# powersupply.net
KiCad netlist of a schematic drawn in Altium Designer
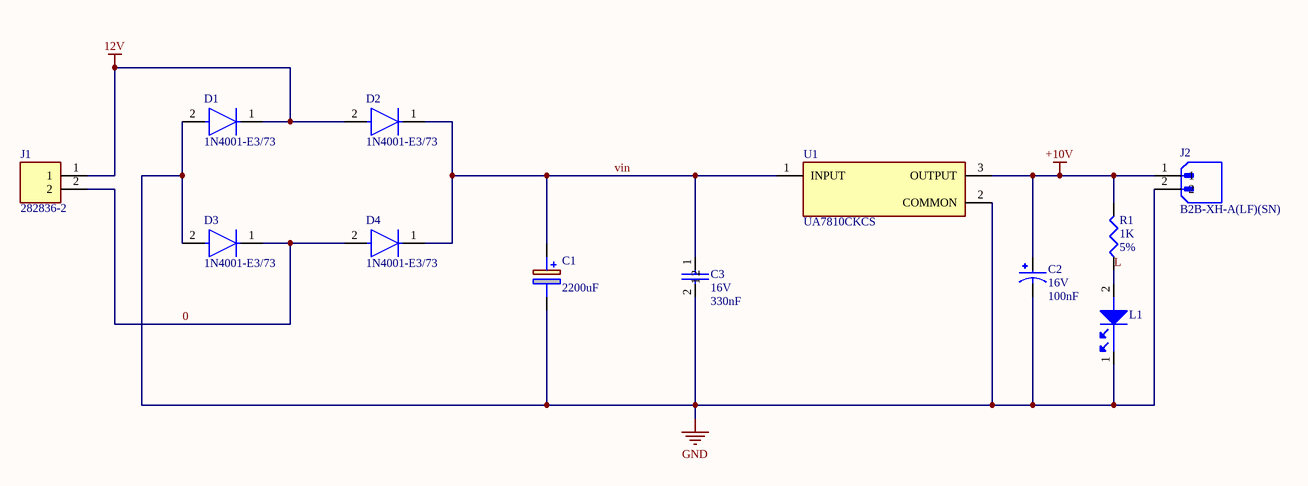
[diagram p0: powersupply.SchDoc]

(export (version "E")
  (design (tool "Eeschema 10.0.6"))
  (components
    (comp (ref "C1")
      (value "2200uF")
      (footprint "CAPPRD500W60D1275H2200")
      (description "Aluminum Electrolytic Capacitors Radial Miniature, Low Impedance, Automotive Grade")
      (fields
        (field (name "MOUSER PART NUMBER") "594-MAL217255222E3")
        (field (name "MANUFACTURER_PART_NUMBER") "MAL217255222E3")
      )
      (libsource (lib "powersupply") (part "MAL217255222E3"))
    )
    (comp (ref "C2")
      (value "100nF")
      (footprint "100nF_Capacitor - duplicate")
      (fields
        (field (name "MANUFACTURER") "Panasonic")
        (field (name "MANUFACTURER PART NUMBER") "EEA-GA1C100")
        (field (name "VOLTAGE") "16V")
        (field (name "CAPACITANCE") "100nF")
      )
      (libsource (lib "powersupply") (part "100nF"))
    )
    (comp (ref "C3")
      (value "330nF")
      (footprint "330nF_Capacitor - duplicate1")
      (description "Ceramic Capacitor, Ceramic, 16V, 10% +Tol, 10% -Tol, SL0, 120ppm/Cel TC, 330nF, Through Hole Mount")
      (fields
        (field (name "MANUFACTURER") "Vishay BCcomponents")
        (field (name "MANUFACTURER PART NUMBER") "S220K25SL0N63L6R")
        (field (name "VOLTAGE") "16V")
        (field (name "CAPACITANCE") "330nF")
      )
      (libsource (lib "powersupply") (part "330nF"))
    )
    (comp (ref "D1")
      (value "1N4001-E3/73")
      (footprint "FP-1N4001-E3-73-MFG")
      (description "DIODE GEN PURP 50V 1A DO204AL")
      (fields
        (field (name "MANUFACTURER") "Vishay")
        (field (name "OCTOPART") "https://octopart.com/1n4001-e3%2F73-vishay-42330130")
      )
      (libsource (lib "powersupply") (part "CMP-02540-000001-1"))
    )
    (comp (ref "D2")
      (value "1N4001-E3/73")
      (footprint "FP-1N4001-E3-73-MFG")
      (description "DIODE GEN PURP 50V 1A DO204AL")
      (fields
        (field (name "MANUFACTURER") "Vishay")
        (field (name "OCTOPART") "https://octopart.com/1n4001-e3%2F73-vishay-42330130")
      )
      (libsource (lib "powersupply") (part "CMP-02540-000001-1"))
    )
    (comp (ref "D3")
      (value "1N4001-E3/73")
      (footprint "FP-1N4001-E3-73-MFG")
      (description "DIODE GEN PURP 50V 1A DO204AL")
      (fields
        (field (name "MANUFACTURER") "Vishay")
        (field (name "OCTOPART") "https://octopart.com/1n4001-e3%2F73-vishay-42330130")
      )
      (libsource (lib "powersupply") (part "CMP-02540-000001-1"))
    )
    (comp (ref "D4")
      (value "1N4001-E3/73")
      (footprint "FP-1N4001-E3-73-MFG")
      (description "DIODE GEN PURP 50V 1A DO204AL")
      (fields
        (field (name "MANUFACTURER") "Vishay")
        (field (name "OCTOPART") "https://octopart.com/1n4001-e3%2F73-vishay-42330130")
      )
      (libsource (lib "powersupply") (part "CMP-02540-000001-1"))
    )
    (comp (ref "J1")
      (value "282836-2")
      (footprint "TE_282836-2")
      (fields (field (name "MF") "TE Connectivity"))
      (libsource (lib "powersupply") (part "282836-2"))
    )
    (comp (ref "J2")
      (value "B2B-XH-A(LF)(SN)")
      (footprint "JST_B2B-XH-A(LF)(SN)")
      (description "Connector Header Through Hole 2 position 0.098 (2.50mm)")
      (fields (field (name "MF") "JST Sales America Inc."))
      (libsource (lib "powersupply") (part "B2B-XH-A(LF)(SN)"))
    )
    (comp (ref "L1")
      (value "WP7113SRD/J4")
      (footprint "LEDRD254W57D500H1070")
      (description "LED Uni-Color SB. Red 660nm 2-Pin T-1 3/4 Bulk")
      (fields (field (name "MANUFACTURER") "Kingbright"))
      (libsource (lib "powersupply") (part "WP7113SRD/J4"))
    )
    (comp (ref "R1")
      (value "CFM12JT1K00")
      (footprint "Resister")
      (description "Fixed Resistor, Carbon Film, 0.5W, 1000ohm, 350V, 5% +/-Tol, -400,0ppm/Cel, Through Hole Mount")
      (fields
        (field (name "MANUFACTURER") "Stackpole Electronics")
        (field (name "POWER") "500mW")
        (field (name "RESISTANCE") "1K")
        (field (name "TOLERANCE") "5%")
      )
      (libsource (lib "powersupply") (part "CFM12JT1K00"))
    )
    (comp (ref "U1")
      (value "UA7810CKCS")
      (footprint "FP-KCS0003B-MFG")
      (description "IC REG LINEAR 10V 1.5A TO220-3")
      (libsource (lib "powersupply") (part "CMP-04917-000126-1"))
    )
  )
  (nets
    (net (code "1") (name "+10V") (class "Default")
      (node (ref "C2") (pin "1") (pinfunction "1_1") (pintype "passive"))
      (node (ref "J2") (pin "1") (pinfunction "1_1") (pintype "passive"))
      (node (ref "R1") (pin "2") (pinfunction "2_2") (pintype "passive"))
      (node (ref "U1") (pin "3") (pinfunction "OUTPUT_3") (pintype "power_in"))
    )
    (net (code "2") (name "/0") (class "Default")
      (node (ref "D3") (pin "1") (pinfunction "C_1") (pintype "passive"))
      (node (ref "D4") (pin "2") (pinfunction "A_2") (pintype "passive"))
      (node (ref "J1") (pin "2") (pinfunction "2_2") (pintype "passive"))
    )
    (net (code "3") (name "/L") (class "Default")
      (node (ref "L1") (pin "2") (pinfunction "2_2") (pintype "passive"))
      (node (ref "R1") (pin "1") (pinfunction "1_1") (pintype "passive"))
    )
    (net (code "4") (name "/vin") (class "Default")
      (node (ref "C1") (pin "1") (pinfunction "+_1") (pintype "passive"))
      (node (ref "C3") (pin "1") (pinfunction "1_1") (pintype "passive"))
      (node (ref "D2") (pin "1") (pinfunction "C_1") (pintype "passive"))
      (node (ref "D4") (pin "1") (pinfunction "C_1") (pintype "passive"))
      (node (ref "U1") (pin "1") (pinfunction "INPUT_1") (pintype "power_in"))
    )
    (net (code "5") (name "12V") (class "Default")
      (node (ref "D1") (pin "1") (pinfunction "C_1") (pintype "passive"))
      (node (ref "D2") (pin "2") (pinfunction "A_2") (pintype "passive"))
      (node (ref "J1") (pin "1") (pinfunction "1_1") (pintype "passive"))
    )
    (net (code "6") (name "GND") (class "Default")
      (node (ref "C1") (pin "2") (pinfunction "-_2") (pintype "passive"))
      (node (ref "C2") (pin "2") (pinfunction "2_2") (pintype "passive"))
      (node (ref "C3") (pin "2") (pinfunction "2_2") (pintype "passive"))
      (node (ref "D1") (pin "2") (pinfunction "A_2") (pintype "passive"))
      (node (ref "D3") (pin "2") (pinfunction "A_2") (pintype "passive"))
      (node (ref "J2") (pin "2") (pinfunction "2_2") (pintype "passive"))
      (node (ref "L1") (pin "1") (pinfunction "1_1") (pintype "passive"))
      (node (ref "U1") (pin "2") (pinfunction "COMMON_2") (pintype "power_in"))
    )
  )
)
